# TOP.net
KiCad netlist of a schematic drawn in Altium Designer
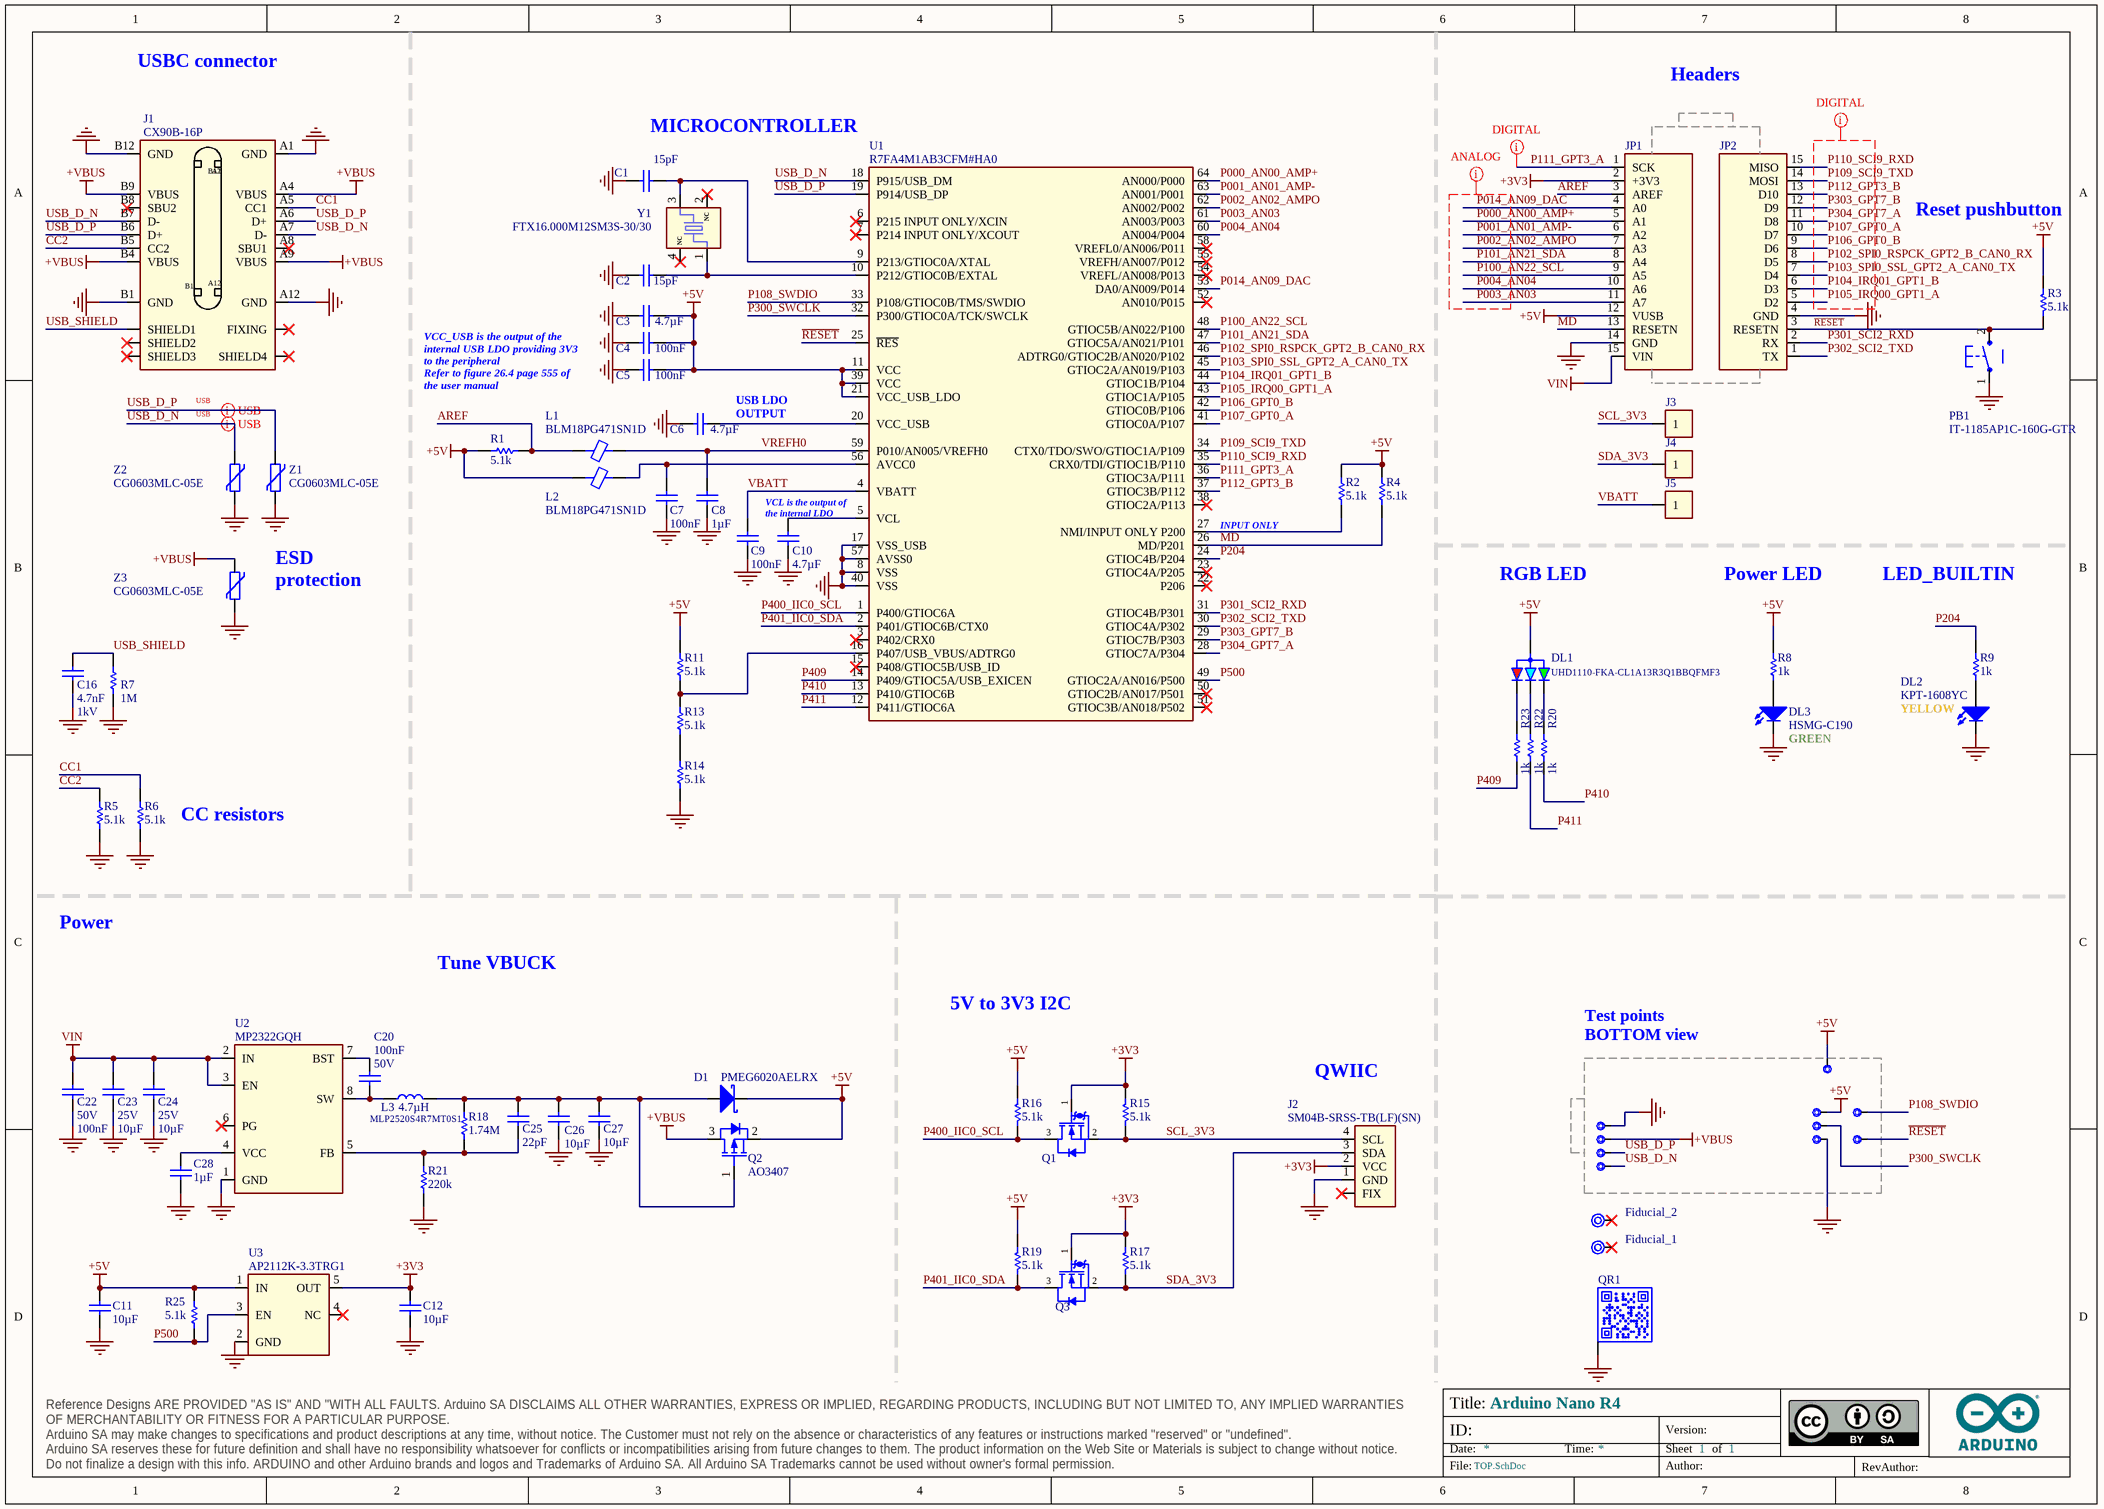
[diagram p0: TOP.SchDoc]

(export (version "E")
  (design (tool "Eeschema 10.0.6"))
  (components
    (comp (ref "3V3")
      (value "Test point 1.00mm")
      (footprint "TP-1.00MM")
      (fields (field (name "MANUFACTURER") "This is not a component"))
      (libsource (lib "Clean") (part "TESTPOINT"))
    )
    (comp (ref "C1")
      (value "15pF")
      (footprint "CAP-0402")
      (description "CAP CHIP 0402 15pF 5% 50V C0G")
      (fields (field (name "PART NUMBER") "C0402C150J5GACTU") (field (name "MANUFACTURER") "KEMET"))
      (libsource (lib "Clean") (part "CAP"))
    )
    (comp (ref "C2")
      (value "15pF")
      (footprint "CAP-0402")
      (description "CAP CHIP 0402 15pF 5% 50V C0G")
      (fields (field (name "PART NUMBER") "C0402C150J5GACTU") (field (name "MANUFACTURER") "KEMET"))
      (libsource (lib "Clean") (part "CAP"))
    )
    (comp (ref "C3")
      (value "4.7µF")
      (footprint "CAP-0402")
      (description "CAP CHIP 0402 4.7uF 20% 6V3 X5R")
      (fields (field (name "TOLERANCE") "20%") (field (name "MANUFACTURER") "Hottech"))
      (libsource (lib "Clean") (part "CAP"))
    )
    (comp (ref "C4")
      (value "100nF")
      (footprint "CAP-0402")
      (description "CAP CHIP 0402 100nF 10% 50V X5R")
      (fields (field (name "TOLERANCE") "10%") (field (name "MANUFACTURER") "Murata"))
      (libsource (lib "Clean") (part "CAP"))
    )
    (comp (ref "C5")
      (value "100nF")
      (footprint "CAP-0402")
      (description "CAP CHIP 0402 100nF 10% 50V X5R")
      (fields (field (name "TOLERANCE") "10%") (field (name "MANUFACTURER") "Murata"))
      (libsource (lib "Clean") (part "CAP"))
    )
    (comp (ref "C6")
      (value "4.7µF")
      (footprint "CAP-0402")
      (description "CAP CHIP 0402 4.7uF 20% 6V3 X5R")
      (fields (field (name "TOLERANCE") "20%") (field (name "MANUFACTURER") "Hottech"))
      (libsource (lib "Clean") (part "CAP"))
    )
    (comp (ref "C7")
      (value "100nF")
      (footprint "CAP-0402")
      (description "CAP CHIP 0402 100nF 10% 50V X5R")
      (fields (field (name "TOLERANCE") "10%") (field (name "MANUFACTURER") "Murata"))
      (libsource (lib "Clean") (part "CAP"))
    )
    (comp (ref "C8")
      (value "1µF")
      (footprint "CAP-0402")
      (description "CAP CHIP 0402 1uF 10% 10V X5R")
      (fields (field (name "TOLERANCE") "10%") (field (name "PART NUMBER") "CL05A105KP5NNNC"))
      (libsource (lib "Clean") (part "CAP"))
    )
    (comp (ref "C9")
      (value "100nF")
      (footprint "CAP-0402")
      (description "CAP CHIP 0402 100nF 10% 50V X5R")
      (fields (field (name "TOLERANCE") "10%") (field (name "MANUFACTURER") "Murata"))
      (libsource (lib "Clean") (part "CAP"))
    )
    (comp (ref "C10")
      (value "4.7µF")
      (footprint "CAP-0402")
      (description "CAP CHIP 0402 4.7uF 20% 6V3 X5R")
      (fields (field (name "TOLERANCE") "20%") (field (name "MANUFACTURER") "Hottech"))
      (libsource (lib "Clean") (part "CAP"))
    )
    (comp (ref "C11")
      (value "10µF")
      (footprint "CAP-0603")
      (description "CAP CHIP 0603 10uF 10% 10V X5R")
      (fields (field (name "MANUFACTURER") "Murata") (field (name "VOLTAGE") "10V"))
      (libsource (lib "Clean") (part "CAP"))
    )
    (comp (ref "C12")
      (value "10µF")
      (footprint "CAP-0603")
      (description "CAP CHIP 0603 10uF 10% 10V X5R")
      (fields (field (name "MANUFACTURER") "Murata") (field (name "VOLTAGE") "10V"))
      (libsource (lib "Clean") (part "CAP"))
    )
    (comp (ref "C16")
      (value "4.7nF")
      (footprint "CAP-0805")
      (description "CAP CHIP 0805 4.7nF 10% 1000V X7R")
      (fields
        (field (name "MANUFACTURER") "PSA Shenzen")
        (field (name "VOLTAGE") "1kV")
        (field (name "TOLERANCE") "10%")
      )
      (libsource (lib "Clean") (part "CAP"))
    )
    (comp (ref "C20")
      (value "100nF")
      (footprint "CAP-0402")
      (description "CAP CHIP 0402 100nF 10% 50V X5R")
      (fields
        (field (name "VOLTAGE") "50V")
        (field (name "PART NUMBER") "GRM155R61H104KE19D")
        (field (name "MANUFACTURER") "Murata")
      )
      (libsource (lib "Clean") (part "CAP"))
    )
    (comp (ref "C22")
      (value "100nF")
      (footprint "CAP-0402")
      (description "CAP CHIP 0402 100nF 10% 50V X5R")
      (fields
        (field (name "MANUFACTURER") "Murata")
        (field (name "PART NUMBER") "GRM155R61H104KE19D")
        (field (name "VOLTAGE") "50V")
      )
      (libsource (lib "Clean") (part "CAP"))
    )
    (comp (ref "C23")
      (value "10µF")
      (footprint "CAP-0603")
      (description "CAP CHIP 0603 10uF 20% 25V X5R")
      (fields
        (field (name "VOLTAGE") "25V")
        (field (name "PART NUMBER") "C1608A106M250NT")
        (field (name "TOLERANCE") "20%")
      )
      (libsource (lib "Clean") (part "CAP"))
    )
    (comp (ref "C24")
      (value "10µF")
      (footprint "CAP-0603")
      (description "CAP CHIP 0603 10uF 20% 25V X5R")
      (fields
        (field (name "VOLTAGE") "25V")
        (field (name "PART NUMBER") "C1608A106M250NT")
        (field (name "TOLERANCE") "20%")
      )
      (libsource (lib "Clean") (part "CAP"))
    )
    (comp (ref "C25")
      (value "22pF")
      (footprint "CAP-0402")
      (description "CAP CHIP 0402 22pF 5% 50V C0G")
      (fields (field (name "TOLERANCE") "5%") (field (name "PART NUMBER") "0402N220J500CT"))
      (libsource (lib "Clean") (part "CAP"))
    )
    (comp (ref "C26")
      (value "10µF")
      (footprint "CAP-0603")
      (description "CAP CHIP 0603 10uF 20% 25V X5R")
      (fields (field (name "VOLTAGE") "25V") (field (name "PART NUMBER") "C1608A106M250NT"))
      (libsource (lib "Clean") (part "CAP"))
    )
    (comp (ref "C27")
      (value "10µF")
      (footprint "CAP-0603")
      (description "CAP CHIP 0603 10uF 20% 25V X5R")
      (fields (field (name "VOLTAGE") "25V") (field (name "PART NUMBER") "C1608A106M250NT"))
      (libsource (lib "Clean") (part "CAP"))
    )
    (comp (ref "C28")
      (value "1µF")
      (footprint "CAP-0402")
      (description "CAP CHIP 0402 1uF 10% 50V X5R")
      (fields (field (name "TOLERANCE") "10%") (field (name "MANUFACTURER") "TDK"))
      (libsource (lib "Clean") (part "CAP"))
    )
    (comp (ref "D+1")
      (value "Test point 1.00mm")
      (footprint "TP-1.00MM")
      (fields (field (name "MANUFACTURER") "This is not a component"))
      (libsource (lib "Clean") (part "TESTPOINT"))
    )
    (comp (ref "D-1")
      (value "Test point 1.00mm")
      (footprint "TP-1.00MM")
      (fields (field (name "MANUFACTURER") "This is not a component"))
      (libsource (lib "Clean") (part "TESTPOINT"))
    )
    (comp (ref "D1")
      (value "PMEG6020AELRX")
      (footprint "SOD123-1")
      (description "DIODE SCHOTTKY SMD 2A 60V SOD123FL")
      (fields (field (name "MANUFACTURER") "Nexperia"))
      (libsource (lib "Clean") (part "PMEG6020AELRX"))
    )
    (comp (ref "DL1")
      (value "UHD1110-FKA-CL1A13R3Q1BBQFMF3")
      (footprint "UHD1110-FKA-CL1A13R3Q1BBQFMF3")
      (description "LED RGB BLACK BODY SMD")
      (fields (field (name "MANUFACTURER") "Cree LED"))
      (libsource (lib "Clean") (part "UHD1110-FKA-CL1A13R3Q1BBQFMF3"))
    )
    (comp (ref "DL2")
      (value "KPT-1608YC")
      (footprint "LEDC1608X80N-AK")
      (description "LED SMD 0603 GIA588   8mcd 120^")
      (fields (field (name "MANUFACTURER") "Kingbright"))
      (libsource (lib "Clean") (part "LED"))
    )
    (comp (ref "DL3")
      (value "HSMG-C190")
      (footprint "LEDC1608X80N-AK")
      (description "LED SMD 0603 GREEN/568 15mcd 120^")
      (fields (field (name "MANUFACTURER") "Broadcom"))
      (libsource (lib "Clean") (part "LED"))
    )
    (comp (ref "Fiducial_1")
      (value "Fiducial mark 1mm with 2mm solder")
      (footprint "Fiducial mark 1mm with circle-Footprint-1")
      (libsource (lib "Clean") (part "Fiducial mark 1mm with circle"))
    )
    (comp (ref "Fiducial_2")
      (value "Fiducial mark 1mm with 2mm solder")
      (footprint "Fiducial mark 1mm with circle-Footprint-1")
      (libsource (lib "Clean") (part "Fiducial mark 1mm with circle"))
    )
    (comp (ref "GND1")
      (value "Test point 1.00mm")
      (footprint "TP-1.00MM")
      (fields (field (name "MANUFACTURER") "This is not a component"))
      (libsource (lib "Clean") (part "TESTPOINT"))
    )
    (comp (ref "GND2")
      (value "Test point 1.00mm")
      (footprint "TP-1.00MM")
      (fields (field (name "MANUFACTURER") "This is not a component"))
      (libsource (lib "Clean") (part "TESTPOINT"))
    )
    (comp (ref "GPIO46")
      (value "Test point 1.00mm")
      (footprint "TP-1.00MM")
      (fields (field (name "MANUFACTURER") "This is not a component"))
      (libsource (lib "Clean") (part "TESTPOINT"))
    )
    (comp (ref "J1")
      (value "CX90B-16P")
      (footprint "CX90B-16P-Footprint-1")
      (description "CONN RCPT USB3.1 TYPEC 16POS SMD")
      (fields (field (name "MANUFACTURER") "Hirose"))
      (libsource (lib "Clean") (part "CX90B-16P-Symbol-1"))
    )
    (comp (ref "J2")
      (value "SM04B-SRSS-TB(LF)(SN)")
      (footprint "SM04B-SRSS-TB(LF)(SN)-Footprint-1")
      (description "CONN JST 4POS SIDE 1MM TIN QWIIC")
      (fields (field (name "MANUFACTURER") "JST"))
      (libsource (lib "Clean") (part "SM04B-SRSS-TB(LF)(SN)"))
    )
    (comp (ref "J3")
      (value "HEADER TH 2.54mm VERT. 1x001POS")
      (footprint "PIN HEADER 2.54mm VERT. 1x1POS")
      (libsource (lib "Clean") (part "PIN HEADER 2.54mm VERT. 1x1POS"))
    )
    (comp (ref "J4")
      (value "HEADER TH 2.54mm VERT. 1x001POS")
      (footprint "PIN HEADER 2.54mm VERT. 1x1POS")
      (libsource (lib "Clean") (part "PIN HEADER 2.54mm VERT. 1x1POS"))
    )
    (comp (ref "J5")
      (value "HEADER TH 2.54mm VERT. 1x001POS")
      (footprint "PIN HEADER 2.54mm VERT. 1x1POS")
      (libsource (lib "Clean") (part "PIN HEADER 2.54mm VERT. 1x1POS"))
    )
    (comp (ref "JP1")
      (value "PINHD-1X15-NANO-ANALOG-CASTELLATED")
      (footprint "PINHD-1X14_5VF")
      (description "CONN THD SOCKET F/1/D 15V JANALOG NANO-TYPE CASTELLATED")
      (libsource (lib "Clean") (part "PINHD-1X15-NANO-ANALOG-CASTELLATED"))
    )
    (comp (ref "JP2")
      (value "PINHD-1X15-NANO-DIGITAL-CASTELLATED")
      (footprint "PINHD-1X14_5VF")
      (description "CONN THD SOCKET F/1/D 15V JDIGITAL NANO-TYPE CASTELLATED")
      (libsource (lib "Clean") (part "PINHD-1X15-NANO-DIGITAL"))
    )
    (comp (ref "L1")
      (value "BLM18PG471SN1D")
      (footprint "L-0603")
      (description "FERRITE SMD 0603 470R 1A 0.2R")
      (fields (field (name "TOLERANCE") "25%") (field (name "MANUFACTURER") "Murata"))
      (libsource (lib "Clean") (part "Ferrite"))
    )
    (comp (ref "L2")
      (value "BLM18PG471SN1D")
      (footprint "L-0603")
      (description "FERRITE SMD 0603 470R 1A 0.2R")
      (fields (field (name "TOLERANCE") "25%") (field (name "MANUFACTURER") "Murata"))
      (libsource (lib "Clean") (part "Ferrite"))
    )
    (comp (ref "L3")
      (value "MLP2520S4R7MT0S1")
      (footprint "INDC2520X10L")
      (description "IND FIXED SMD 4.7UH 1A 130mOHM")
      (fields
        (field (name "TOLERANCE") "20%")
        (field (name "MANUFACTURER") "TDK")
        (field (name "ALTIUM_VALUE") "4.7µH")
      )
      (libsource (lib "Clean") (part "Inductor"))
    )
    (comp (ref "NC1")
      (value "Test point 1.00mm")
      (footprint "TP-1.00MM")
      (fields (field (name "MANUFACTURER") "This is not a component"))
      (libsource (lib "Clean") (part "TESTPOINT"))
    )
    (comp (ref "NC2")
      (value "Test point 1.00mm")
      (footprint "TP-1.00MM")
      (fields (field (name "MANUFACTURER") "This is not a component"))
      (libsource (lib "Clean") (part "TESTPOINT"))
    )
    (comp (ref "PB1")
      (value "IT-1185AP1C-160G-GTR")
      (footprint "C&K_PTS820_NO_HOLES-1")
      (description "PUSHBUTTON WHITE NO ANCHORS")
      (fields (field (name "MANUFACTURER") "Switronic"))
      (libsource (lib "Clean") (part "PTS820"))
    )
    (comp (ref "Q1")
      (value "2N7002KT1G")
      (footprint "SOT23")
      (description "MOSFET N-CH 60V 300mA ESD prot. SOT23")
      (fields (field (name "MANUFACTURER") "On Semiconductor"))
      (libsource (lib "Clean") (part "NMOS-2"))
    )
    (comp (ref "Q2")
      (value "AO3407")
      (footprint "SOT23-3")
      (description "MOSFET P-CH 30V 3.5A SOT23 VGSmin=1.4-2.4V RDSon max 87mOhm (-4.5V)")
      (fields (field (name "MANUFACTURER") "Hottech"))
      (libsource (lib "Clean") (part "AO3407"))
    )
    (comp (ref "Q3")
      (value "2N7002KT1G")
      (footprint "SOT23")
      (description "MOSFET N-CH 60V 300mA ESD prot. SOT23")
      (fields (field (name "MANUFACTURER") "On Semiconductor"))
      (libsource (lib "Clean") (part "NMOS-2"))
    )
    (comp (ref "QR1")
      (value "QR CODE 4x4mm")
      (footprint "QR CODE 4x4mm")
      (description "QR CODE 4x4mm on layer 34 (This is not a component)")
      (fields (field (name "PART NUMBER") "This is not a component"))
      (libsource (lib "Clean") (part "QR CODE 4x4mm"))
    )
    (comp (ref "R1")
      (value "5.1k")
      (footprint "RES-0402")
      (description "RES CHIP 0402 5k1 1% 1/16W")
      (fields (field (name "TOLERANCE") "1%") (field (name "POWER") "62.5mW"))
      (libsource (lib "Clean") (part "RES"))
    )
    (comp (ref "R2")
      (value "5.1k")
      (footprint "RES-0402")
      (description "RES CHIP 0402 5k1 1% 1/16W")
      (fields (field (name "TOLERANCE") "1%") (field (name "MANUFACTURER") "YAGEO"))
      (libsource (lib "Clean") (part "RES"))
    )
    (comp (ref "R3")
      (value "5.1k")
      (footprint "RES-0402")
      (description "RES CHIP 0402 5k1 1% 1/16W")
      (fields (field (name "PART NUMBER") "RC0402FR-075K1L") (field (name "MANUFACTURER") "YAGEO"))
      (libsource (lib "Clean") (part "RES"))
    )
    (comp (ref "R4")
      (value "5.1k")
      (footprint "RES-0402")
      (description "RES CHIP 0402 5k1 1% 1/16W")
      (fields (field (name "TOLERANCE") "1%") (field (name "MANUFACTURER") "YAGEO"))
      (libsource (lib "Clean") (part "RES"))
    )
    (comp (ref "R5")
      (value "5.1k")
      (footprint "RES-0402")
      (description "RES CHIP 0402 5k1 1% 1/16W")
      (fields (field (name "POWER") "62.5mW") (field (name "MANUFACTURER") "YAGEO"))
      (libsource (lib "Clean") (part "RES"))
    )
    (comp (ref "R6")
      (value "5.1k")
      (footprint "RES-0402")
      (description "RES CHIP 0402 5k1 1% 1/16W")
      (fields (field (name "POWER") "62.5mW") (field (name "MANUFACTURER") "YAGEO"))
      (libsource (lib "Clean") (part "RES"))
    )
    (comp (ref "R7")
      (value "1M")
      (footprint "RES-0402")
      (description "RES CHIP 0402 1M 1% 1/16W")
      (fields (field (name "MANUFACTURER") "Vishay") (field (name "POWER") "62.5mW"))
      (libsource (lib "Clean") (part "RES"))
    )
    (comp (ref "R8")
      (value "1k")
      (footprint "RES-0402")
      (description "RES CHIP 0402 1k 1% 1/16W")
      (fields (field (name "PART NUMBER") "CRCW04021K00FKEDC") (field (name "TOLERANCE") "1%"))
      (libsource (lib "Clean") (part "RES"))
    )
    (comp (ref "R9")
      (value "1k")
      (footprint "RES-0402")
      (description "RES CHIP 0402 1k 1% 1/16W")
      (fields (field (name "PART NUMBER") "CRCW04021K00FKEDC") (field (name "TOLERANCE") "1%"))
      (libsource (lib "Clean") (part "RES"))
    )
    (comp (ref "R11")
      (value "5.1k")
      (footprint "RES-0402")
      (description "RES CHIP 0402 5k1 1% 1/16W")
      (fields (field (name "PART NUMBER") "RC0402FR-075K1L") (field (name "MANUFACTURER") "YAGEO"))
      (libsource (lib "Clean") (part "RES"))
    )
    (comp (ref "R13")
      (value "5.1k")
      (footprint "RES-0402")
      (description "RES CHIP 0402 5k1 1% 1/16W")
      (fields (field (name "PART NUMBER") "RC0402FR-075K1L") (field (name "MANUFACTURER") "YAGEO"))
      (libsource (lib "Clean") (part "RES"))
    )
    (comp (ref "R14")
      (value "5.1k")
      (footprint "RES-0402")
      (description "RES CHIP 0402 5k1 1% 1/16W")
      (fields (field (name "PART NUMBER") "RC0402FR-075K1L") (field (name "MANUFACTURER") "YAGEO"))
      (libsource (lib "Clean") (part "RES"))
    )
    (comp (ref "R15")
      (value "5.1k")
      (footprint "RES-0402")
      (description "RES CHIP 0402 5k1 1% 1/16W")
      (fields (field (name "TOLERANCE") "1%") (field (name "MANUFACTURER") "YAGEO"))
      (libsource (lib "Clean") (part "RES"))
    )
    (comp (ref "R16")
      (value "5.1k")
      (footprint "RES-0402")
      (description "RES CHIP 0402 5k1 1% 1/16W")
      (fields (field (name "TOLERANCE") "1%") (field (name "MANUFACTURER") "YAGEO"))
      (libsource (lib "Clean") (part "RES"))
    )
    (comp (ref "R17")
      (value "5.1k")
      (footprint "RES-0402")
      (description "RES CHIP 0402 5k1 1% 1/16W")
      (fields (field (name "TOLERANCE") "1%") (field (name "MANUFACTURER") "YAGEO"))
      (libsource (lib "Clean") (part "RES"))
    )
    (comp (ref "R18")
      (value "1.74M")
      (footprint "RES-0402")
      (description "RES CHIP 0402 1.74M 1% 1/16W")
      (fields (field (name "MANUFACTURER") "YAGEO") (field (name "TOLERANCE") "1%"))
      (libsource (lib "Clean") (part "RES"))
    )
    (comp (ref "R19")
      (value "5.1k")
      (footprint "RES-0402")
      (description "RES CHIP 0402 5k1 1% 1/16W")
      (fields (field (name "TOLERANCE") "1%") (field (name "MANUFACTURER") "YAGEO"))
      (libsource (lib "Clean") (part "RES"))
    )
    (comp (ref "R20")
      (value "1k")
      (footprint "RES-0402")
      (description "RES CHIP 0402 1k 1% 1/16W")
      (fields (field (name "PART NUMBER") "CRCW04021K00FKEDC") (field (name "TOLERANCE") "1%"))
      (libsource (lib "Clean") (part "RES"))
    )
    (comp (ref "R21")
      (value "220k")
      (footprint "RES-0402")
      (description "RES CHIP 0402 220k 1% 1/16W")
      (fields (field (name "MANUFACTURER") "Vishay") (field (name "PART NUMBER") "CRCW0402220KFKED"))
      (libsource (lib "Clean") (part "RES"))
    )
    (comp (ref "R22")
      (value "1k")
      (footprint "RES-0402")
      (description "RES CHIP 0402 1k 1% 1/16W")
      (fields (field (name "PART NUMBER") "CRCW04021K00FKEDC") (field (name "TOLERANCE") "1%"))
      (libsource (lib "Clean") (part "RES"))
    )
    (comp (ref "R23")
      (value "1k")
      (footprint "RES-0402")
      (description "RES CHIP 0402 1k 1% 1/16W")
      (fields (field (name "PART NUMBER") "CRCW04021K00FKEDC") (field (name "TOLERANCE") "1%"))
      (libsource (lib "Clean") (part "RES"))
    )
    (comp (ref "R25")
      (value "5.1k")
      (footprint "RES-0402")
      (description "RES CHIP 0402 5k1 1% 1/16W")
      (fields (field (name "PART NUMBER") "RC0402FR-075K1L") (field (name "MANUFACTURER") "YAGEO"))
      (libsource (lib "Clean") (part "RES"))
    )
    (comp (ref "TP_VUSB")
      (value "Test point 1.00mm")
      (footprint "TP-1.00MM")
      (fields (field (name "MANUFACTURER") "This is not a component"))
      (libsource (lib "Clean") (part "TESTPOINT"))
    )
    (comp (ref "U1")
      (value "R7FA4M1AB3CFM#HA0")
      (footprint "CQFP50P1200X1200X170-64L")
      (description "IC uC RA4M1 32b M4 48MHz 254KB flash 32KB RAM 105°C LQFP64 10x10mm")
      (fields (field (name "MANUFACTURER") "Renesas"))
      (libsource (lib "Clean") (part "R7FA4M1AB3CFM#HA0"))
    )
    (comp (ref "U2")
      (value "MP2322GQH")
      (footprint "QFN50P150X200X90-8L")
      (description "IC STEP DOWN CONV 1A 22V QFN8")
      (fields (field (name "MANUFACTURER") "Monolithic Power Systems"))
      (libsource (lib "Clean") (part "MP2322GQH"))
    )
    (comp (ref "U3")
      (value "AP2112K-3.3TRG1")
      (footprint "SOT25")
      (description "IC LDO Vin max 6.5V Vout 3V3 Iout 600mA +EN  SOT25")
      (fields (field (name "MANUFACTURER") "Diodes Inc"))
      (libsource (lib "Clean") (part "AP2112K-3.3TRG1"))
    )
    (comp (ref "VUSB")
      (value "Test point 1.00mm")
      (footprint "TP-1.00MM")
      (fields (field (name "MANUFACTURER") "This is not a component"))
      (libsource (lib "Clean") (part "TESTPOINT"))
    )
    (comp (ref "Y1")
      (value "FTX16.000M12SM3S-30/30")
      (footprint "CRYSTAL_3.2x2.5mm_16MHz")
      (description "CRYSTAL 16.0000MHz 12pF SMD")
      (fields (field (name "MANUFACTURER") "Fronter Electronics"))
      (libsource (lib "Clean") (part "Crystal 4 pin 1-3"))
    )
    (comp (ref "Z1")
      (value "CG0603MLC-05E")
      (footprint "0603")
      (description "VARISTOR SMD 0603 VDC 5V ESD PROTECTION")
      (fields (field (name "MANUFACTURER") "Bourns") (field (name "VOLTAGE") "5V"))
      (libsource (lib "Clean") (part "Symbol"))
    )
    (comp (ref "Z2")
      (value "CG0603MLC-05E")
      (footprint "0603")
      (description "VARISTOR SMD 0603 VDC 5V ESD PROTECTION")
      (fields (field (name "MANUFACTURER") "Bourns") (field (name "VOLTAGE") "5V"))
      (libsource (lib "Clean") (part "Symbol"))
    )
    (comp (ref "Z3")
      (value "CG0603MLC-05E")
      (footprint "0603")
      (description "VARISTOR SMD 0603 VDC 5V ESD PROTECTION")
      (fields (field (name "MANUFACTURER") "Bourns") (field (name "VOLTAGE") "5V"))
      (libsource (lib "Clean") (part "Symbol"))
    )
  )
  (nets
    (net (code "1") (name "+3V3") (class "Default")
      (node (ref "C12") (pin "2") (pinfunction "2_2") (pintype "passive"))
      (node (ref "J2") (pin "2") (pinfunction "VCC_2") (pintype "passive"))
      (node (ref "JP1") (pin "2") (pinfunction "+3V3_2") (pintype "passive"))
      (node (ref "Q1") (pin "1") (pinfunction "G_1") (pintype "passive"))
      (node (ref "Q3") (pin "1") (pinfunction "G_1") (pintype "passive"))
      (node (ref "R15") (pin "1") (pinfunction "1_1") (pintype "passive"))
      (node (ref "R17") (pin "1") (pinfunction "1_1") (pintype "passive"))
      (node (ref "U3") (pin "5") (pinfunction "OUT_5") (pintype "power_in"))
    )
    (net (code "2") (name "+5V") (class "Default")
      (node (ref "3V3") (pin "X") (pinfunction "X_X") (pintype "passive"))
      (node (ref "C11") (pin "2") (pinfunction "2_2") (pintype "passive"))
      (node (ref "C3") (pin "2") (pinfunction "2_2") (pintype "passive"))
      (node (ref "C4") (pin "2") (pinfunction "2_2") (pintype "passive"))
      (node (ref "C5") (pin "2") (pinfunction "2_2") (pintype "passive"))
      (node (ref "D1") (pin "C") (pinfunction "C_C") (pintype "passive"))
      (node (ref "DL1") (pin "4") (pinfunction "ANODE_4") (pintype "passive"))
      (node (ref "JP1") (pin "12") (pinfunction "VUSB_12") (pintype "passive"))
      (node (ref "L2") (pin "1") (pinfunction "1_1") (pintype "passive"))
      (node (ref "Q2") (pin "2") (pinfunction "S_2") (pintype "passive"))
      (node (ref "R1") (pin "2") (pinfunction "2_2") (pintype "passive"))
      (node (ref "R11") (pin "2") (pinfunction "2_2") (pintype "passive"))
      (node (ref "R16") (pin "1") (pinfunction "1_1") (pintype "passive"))
      (node (ref "R19") (pin "1") (pinfunction "1_1") (pintype "passive"))
      (node (ref "R2") (pin "1") (pinfunction "1_1") (pintype "passive"))
      (node (ref "R25") (pin "2") (pinfunction "2_2") (pintype "passive"))
      (node (ref "R3") (pin "2") (pinfunction "2_2") (pintype "passive"))
      (node (ref "R4") (pin "1") (pinfunction "1_1") (pintype "passive"))
      (node (ref "R8") (pin "2") (pinfunction "2_2") (pintype "passive"))
      (node (ref "U1") (pin "11") (pinfunction "VCC_11") (pintype "passive"))
      (node (ref "U1") (pin "21") (pinfunction "VCC_USB_LDO_21") (pintype "passive"))
      (node (ref "U1") (pin "39") (pinfunction "VCC_39") (pintype "passive"))
      (node (ref "U3") (pin "1") (pinfunction "IN_1") (pintype "power_in"))
      (node (ref "VUSB") (pin "X") (pinfunction "X_X") (pintype "passive"))
    )
    (net (code "3") (name "+VBUS") (class "Default")
      (node (ref "J1") (pin "A4") (pinfunction "VBUS_A4") (pintype "passive"))
      (node (ref "J1") (pin "A9") (pinfunction "VBUS_A9") (pintype "passive"))
      (node (ref "J1") (pin "B4") (pinfunction "VBUS_B4") (pintype "passive"))
      (node (ref "J1") (pin "B9") (pinfunction "VBUS_B9") (pintype "passive"))
      (node (ref "Q2") (pin "3") (pinfunction "D_3") (pintype "passive"))
      (node (ref "TP_VUSB") (pin "X") (pinfunction "X_X") (pintype "passive"))
      (node (ref "Z3") (pin "1") (pinfunction "1_1") (pintype "passive"))
    )
    (net (code "4") (name "/AREF") (class "Default")
      (node (ref "JP1") (pin "3") (pinfunction "AREF_3") (pintype "passive"))
      (node (ref "L1") (pin "1") (pinfunction "1_1") (pintype "passive"))
      (node (ref "R1") (pin "1") (pinfunction "1_1") (pintype "passive"))
    )
    (net (code "5") (name "/CC1") (class "Default")
      (node (ref "J1") (pin "A5") (pinfunction "CC1_A5") (pintype "passive"))
      (node (ref "R6") (pin "2") (pinfunction "2_2") (pintype "passive"))
    )
    (net (code "6") (name "/CC2") (class "Default")
      (node (ref "J1") (pin "B5") (pinfunction "CC2_B5") (pintype "passive"))
      (node (ref "R5") (pin "2") (pinfunction "2_2") (pintype "passive"))
    )
    (net (code "7") (name "/MD") (class "Default")
      (node (ref "JP1") (pin "13") (pinfunction "RESETN_13") (pintype "passive"))
      (node (ref "R4") (pin "2") (pinfunction "2_2") (pintype "passive"))
      (node (ref "U1") (pin "26") (pinfunction "MD/P201_26") (pintype "passive"))
    )
    (net (code "8") (name "/P000_AN00_AMP+") (class "Default")
      (node (ref "JP1") (pin "5") (pinfunction "A1_5") (pintype "passive"))
      (node (ref "U1") (pin "64") (pinfunction "AN000/P000_64") (pintype "passive"))
    )
    (net (code "9") (name "/P001_AN01_AMP-") (class "Default")
      (node (ref "JP1") (pin "6") (pinfunction "A2_6") (pintype "passive"))
      (node (ref "U1") (pin "63") (pinfunction "AN001/P001_63") (pintype "passive"))
    )
    (net (code "10") (name "/P002_AN02_AMPO") (class "Default")
      (node (ref "JP1") (pin "7") (pinfunction "A3_7") (pintype "passive"))
      (node (ref "U1") (pin "62") (pinfunction "AN002/P002_62") (pintype "passive"))
    )
    (net (code "11") (name "/P003_AN03") (class "Default")
      (node (ref "JP1") (pin "11") (pinfunction "A7_11") (pintype "passive"))
      (node (ref "U1") (pin "61") (pinfunction "AN003/P003_61") (pintype "passive"))
    )
    (net (code "12") (name "/P004_AN04") (class "Default")
      (node (ref "JP1") (pin "10") (pinfunction "A6_10") (pintype "passive"))
      (node (ref "U1") (pin "60") (pinfunction "AN004/P004_60") (pintype "passive"))
    )
    (net (code "13") (name "/P014_AN09_DAC") (class "Default")
      (node (ref "JP1") (pin "4") (pinfunction "A0_4") (pintype "passive"))
      (node (ref "U1") (pin "53") (pinfunction "DA0/AN009/P014_53") (pintype "passive"))
    )
    (net (code "14") (name "/P100_AN22_SCL") (class "Default")
      (node (ref "JP1") (pin "9") (pinfunction "A5_9") (pintype "passive"))
      (node (ref "U1") (pin "48") (pinfunction "GTIOC5B/AN022/P100_48") (pintype "passive"))
    )
    (net (code "15") (name "/P101_AN21_SDA") (class "Default")
      (node (ref "JP1") (pin "8") (pinfunction "A4_8") (pintype "passive"))
      (node (ref "U1") (pin "47") (pinfunction "GTIOC5A/AN021/P101_47") (pintype "passive"))
    )
    (net (code "16") (name "/P102_SPI0_RSPCK_GPT2_B_CAN0_RX") (class "Default")
      (node (ref "JP2") (pin "8") (pinfunction "D5_8") (pintype "passive"))
      (node (ref "U1") (pin "46") (pinfunction "ADTRG0/GTIOC2B/AN020/P102_46") (pintype "passive"))
    )
    (net (code "17") (name "/P103_SPI0_SSL_GPT2_A_CAN0_TX") (class "Default")
      (node (ref "JP2") (pin "7") (pinfunction "D4_7") (pintype "passive"))
      (node (ref "U1") (pin "45") (pinfunction "GTIOC2A/AN019/P103_45") (pintype "passive"))
    )
    (net (code "18") (name "/P104_IRQ01_GPT1_B") (class "Default")
      (node (ref "JP2") (pin "6") (pinfunction "D3_6") (pintype "passive"))
      (node (ref "U1") (pin "44") (pinfunction "GTIOC1B/P104_44") (pintype "passive"))
    )
    (net (code "19") (name "/P105_IRQ00_GPT1_A") (class "Default")
      (node (ref "JP2") (pin "5") (pinfunction "D2_5") (pintype "passive"))
      (node (ref "U1") (pin "43") (pinfunction "GTIOC1A/P105_43") (pintype "passive"))
    )
    (net (code "20") (name "/P106_GPT0_B") (class "Default")
      (node (ref "JP2") (pin "9") (pinfunction "D6_9") (pintype "passive"))
      (node (ref "U1") (pin "42") (pinfunction "GTIOC0B/P106_42") (pintype "passive"))
    )
    (net (code "21") (name "/P107_GPT0_A") (class "Default")
      (node (ref "JP2") (pin "10") (pinfunction "D7_10") (pintype "passive"))
      (node (ref "U1") (pin "41") (pinfunction "GTIOC0A/P107_41") (pintype "passive"))
    )
    (net (code "22") (name "/P108_SWDIO") (class "Default")
      (node (ref "NC1") (pin "X") (pinfunction "X_X") (pintype "passive"))
      (node (ref "U1") (pin "33") (pinfunction "P108/GTIOC0B/TMS/SWDIO_33") (pintype "passive"))
    )
    (net (code "23") (name "/P109_SCI9_TXD") (class "Default")
      (node (ref "JP2") (pin "14") (pinfunction "MOSI_14") (pintype "passive"))
      (node (ref "U1") (pin "34") (pinfunction "CTX0/TDO/SWO/GTIOC1A/P109_34") (pintype "passive"))
    )
    (net (code "24") (name "/P110_SCI9_RXD") (class "Default")
      (node (ref "JP2") (pin "15") (pinfunction "MISO_15") (pintype "passive"))
      (node (ref "U1") (pin "35") (pinfunction "CRX0/TDI/GTIOC1B/P110_35") (pintype "passive"))
    )
    (net (code "25") (name "/P111_GPT3_A") (class "Default")
      (node (ref "JP1") (pin "1") (pinfunction "SCK_1") (pintype "passive"))
      (node (ref "U1") (pin "36") (pinfunction "GTIOC3A/P111_36") (pintype "passive"))
    )
    (net (code "26") (name "/P112_GPT3_B") (class "Default")
      (node (ref "JP2") (pin "13") (pinfunction "D10_13") (pintype "passive"))
      (node (ref "U1") (pin "37") (pinfunction "GTIOC3B/P112_37") (pintype "passive"))
    )
    (net (code "27") (name "/P204") (class "Default")
      (node (ref "R9") (pin "2") (pinfunction "2_2") (pintype "passive"))
      (node (ref "U1") (pin "24") (pinfunction "GTIOC4B/P204_24") (pintype "passive"))
    )
    (net (code "28") (name "/P300_SWCLK") (class "Default")
      (node (ref "GPIO46") (pin "X") (pinfunction "X_X") (pintype "passive"))
      (node (ref "U1") (pin "32") (pinfunction "P300/GTIOC0A/TCK/SWCLK_32") (pintype "passive"))
    )
    (net (code "29") (name "/P301_SCI2_RXD") (class "Default")
      (node (ref "JP2") (pin "2") (pinfunction "RX_2") (pintype "passive"))
      (node (ref "U1") (pin "31") (pinfunction "GTIOC4B/P301_31") (pintype "passive"))
    )
    (net (code "30") (name "/P302_SCI2_TXD") (class "Default")
      (node (ref "JP2") (pin "1") (pinfunction "TX_1") (pintype "passive"))
      (node (ref "U1") (pin "30") (pinfunction "GTIOC4A/P302_30") (pintype "passive"))
    )
    (net (code "31") (name "/P303_GPT7_B") (class "Default")
      (node (ref "JP2") (pin "12") (pinfunction "D9_12") (pintype "passive"))
      (node (ref "U1") (pin "29") (pinfunction "GTIOC7B/P303_29") (pintype "passive"))
    )
    (net (code "32") (name "/P304_GPT7_A") (class "Default")
      (node (ref "JP2") (pin "11") (pinfunction "D8_11") (pintype "passive"))
      (node (ref "U1") (pin "28") (pinfunction "GTIOC7A/P304_28") (pintype "passive"))
    )
    (net (code "33") (name "/P400_IIC0_SCL") (class "Default")
      (node (ref "Q1") (pin "3") (pinfunction "D_3") (pintype "passive"))
      (node (ref "R16") (pin "2") (pinfunction "2_2") (pintype "passive"))
      (node (ref "U1") (pin "1") (pinfunction "P400/GTIOC6A_1") (pintype "passive"))
    )
    (net (code "34") (name "/P401_IIC0_SDA") (class "Default")
      (node (ref "Q3") (pin "3") (pinfunction "D_3") (pintype "passive"))
      (node (ref "R19") (pin "2") (pinfunction "2_2") (pintype "passive"))
      (node (ref "U1") (pin "2") (pinfunction "P401/GTIOC6B/CTX0_2") (pintype "passive"))
    )
    (net (code "35") (name "/P409") (class "Default")
      (node (ref "R23") (pin "1") (pinfunction "1_1") (pintype "passive"))
      (node (ref "U1") (pin "14") (pinfunction "P409/GTIOC5A/USB_EXICEN_14") (pintype "passive"))
    )
    (net (code "36") (name "/P410") (class "Default")
      (node (ref "R20") (pin "1") (pinfunction "1_1") (pintype "passive"))
      (node (ref "U1") (pin "13") (pinfunction "P410/GTIOC6B_13") (pintype "passive"))
    )
    (net (code "37") (name "/P411") (class "Default")
      (node (ref "R22") (pin "1") (pinfunction "1_1") (pintype "passive"))
      (node (ref "U1") (pin "12") (pinfunction "P411/GTIOC6A_12") (pintype "passive"))
    )
    (net (code "38") (name "/P500") (class "Default")
      (node (ref "R25") (pin "1") (pinfunction "1_1") (pintype "passive"))
      (node (ref "U1") (pin "49") (pinfunction "GTIOC2A/AN016/P500_49") (pintype "passive"))
      (node (ref "U3") (pin "3") (pinfunction "EN_3") (pintype "passive"))
    )
    (net (code "39") (name "/SCL_3V3") (class "Default")
      (node (ref "J2") (pin "4") (pinfunction "SCL_4") (pintype "passive"))
      (node (ref "J3") (pin "1") (pinfunction "1_1") (pintype "passive"))
      (node (ref "Q1") (pin "2") (pinfunction "S_2") (pintype "passive"))
      (node (ref "R15") (pin "2") (pinfunction "2_2") (pintype "passive"))
    )
    (net (code "40") (name "/SDA_3V3") (class "Default")
      (node (ref "J2") (pin "3") (pinfunction "SDA_3") (pintype "passive"))
      (node (ref "J4") (pin "1") (pinfunction "1_1") (pintype "passive"))
      (node (ref "Q3") (pin "2") (pinfunction "S_2") (pintype "passive"))
      (node (ref "R17") (pin "2") (pinfunction "2_2") (pintype "passive"))
    )
    (net (code "41") (name "/USB_D_N") (class "Default")
      (node (ref "D-1") (pin "X") (pinfunction "X_X") (pintype "passive"))
      (node (ref "J1") (pin "A7") (pinfunction "D-_A7") (pintype "passive"))
      (node (ref "J1") (pin "B7") (pinfunction "D-_B7") (pintype "passive"))
      (node (ref "U1") (pin "18") (pinfunction "P915/USB_DM_18") (pintype "passive"))
      (node (ref "Z2") (pin "1") (pinfunction "1_1") (pintype "passive"))
    )
    (net (code "42") (name "/USB_D_P") (class "Default")
      (node (ref "D+1") (pin "X") (pinfunction "X_X") (pintype "passive"))
      (node (ref "J1") (pin "A6") (pinfunction "D+_A6") (pintype "passive"))
      (node (ref "J1") (pin "B6") (pinfunction "D+_B6") (pintype "passive"))
      (node (ref "U1") (pin "19") (pinfunction "P914/USB_DP_19") (pintype "passive"))
      (node (ref "Z1") (pin "1") (pinfunction "1_1") (pintype "passive"))
    )
    (net (code "43") (name "/USB_SHIELD") (class "Default")
      (node (ref "C16") (pin "2") (pinfunction "2_2") (pintype "passive"))
      (node (ref "J1") (pin "SHIELD1") (pinfunction "SHIELD1_SHIELD1") (pintype "passive"))
      (node (ref "R7") (pin "2") (pinfunction "2_2") (pintype "passive"))
    )
    (net (code "44") (name "/VBATT") (class "Default")
      (node (ref "C9") (pin "2") (pinfunction "2_2") (pintype "passive"))
      (node (ref "J5") (pin "1") (pinfunction "1_1") (pintype "passive"))
      (node (ref "U1") (pin "4") (pinfunction "VBATT_4") (pintype "passive"))
    )
    (net (code "45") (name "/VREFH0") (class "Default")
      (node (ref "C8") (pin "1") (pinfunction "1_1") (pintype "passive"))
      (node (ref "L1") (pin "2") (pinfunction "2_2") (pintype "passive"))
      (node (ref "U1") (pin "59") (pinfunction "P010/AN005/VREFH0_59") (pintype "passive"))
    )
    (net (code "46") (name "/~{RESET}") (class "Default")
      (node (ref "JP2") (pin "3") (pinfunction "RESETN_3") (pintype "passive"))
      (node (ref "NC2") (pin "X") (pinfunction "X_X") (pintype "passive"))
      (node (ref "PB1") (pin "2") (pinfunction "2_2") (pintype "passive"))
      (node (ref "R3") (pin "1") (pinfunction "1_1") (pintype "passive"))
      (node (ref "U1") (pin "25") (pinfunction "~{RES}_25") (pintype "passive"))
    )
    (net (code "47") (name "GND") (class "Default")
      (node (ref "C1") (pin "2") (pinfunction "2_2") (pintype "passive"))
      (node (ref "C10") (pin "1") (pinfunction "1_1") (pintype "passive"))
      (node (ref "C11") (pin "1") (pinfunction "1_1") (pintype "passive"))
      (node (ref "C12") (pin "1") (pinfunction "1_1") (pintype "passive"))
      (node (ref "C16") (pin "1") (pinfunction "1_1") (pintype "passive"))
      (node (ref "C2") (pin "2") (pinfunction "2_2") (pintype "passive"))
      (node (ref "C22") (pin "2") (pinfunction "2_2") (pintype "passive"))
      (node (ref "C23") (pin "1") (pinfunction "1_1") (pintype "passive"))
      (node (ref "C24") (pin "1") (pinfunction "1_1") (pintype "passive"))
      (node (ref "C26") (pin "1") (pinfunction "1_1") (pintype "passive"))
      (node (ref "C27") (pin "1") (pinfunction "1_1") (pintype "passive"))
      (node (ref "C28") (pin "1") (pinfunction "1_1") (pintype "passive"))
      (node (ref "C3") (pin "1") (pinfunction "1_1") (pintype "passive"))
      (node (ref "C4") (pin "1") (pinfunction "1_1") (pintype "passive"))
      (node (ref "C5") (pin "1") (pinfunction "1_1") (pintype "passive"))
      (node (ref "C6") (pin "1") (pinfunction "1_1") (pintype "passive"))
      (node (ref "C7") (pin "1") (pinfunction "1_1") (pintype "passive"))
      (node (ref "C8") (pin "2") (pinfunction "2_2") (pintype "passive"))
      (node (ref "C9") (pin "1") (pinfunction "1_1") (pintype "passive"))
      (node (ref "DL2") (pin "C") (pinfunction "C_C") (pintype "passive"))
      (node (ref "DL3") (pin "C") (pinfunction "C_C") (pintype "passive"))
      (node (ref "GND1") (pin "X") (pinfunction "X_X") (pintype "passive"))
      (node (ref "GND2") (pin "X") (pinfunction "X_X") (pintype "passive"))
      (node (ref "J1") (pin "A1") (pinfunction "GND_A1") (pintype "passive"))
      (node (ref "J1") (pin "A12") (pinfunction "GND_A12") (pintype "passive"))
      (node (ref "J1") (pin "B1") (pinfunction "GND_B1") (pintype "passive"))
      (node (ref "J1") (pin "B12") (pinfunction "GND_B12") (pintype "passive"))
      (node (ref "J2") (pin "1") (pinfunction "GND_1") (pintype "passive"))
      (node (ref "JP1") (pin "14") (pinfunction "GND_14") (pintype "passive"))
      (node (ref "JP2") (pin "4") (pinfunction "GND_4") (pintype "passive"))
      (node (ref "PB1") (pin "1") (pinfunction "1_1") (pintype "passive"))
      (node (ref "QR1") (pin "PAD") (pinfunction "PAD_PAD") (pintype "passive"))
      (node (ref "R14") (pin "1") (pinfunction "1_1") (pintype "passive"))
      (node (ref "R21") (pin "1") (pinfunction "1_1") (pintype "passive"))
      (node (ref "R5") (pin "1") (pinfunction "1_1") (pintype "passive"))
      (node (ref "R6") (pin "1") (pinfunction "1_1") (pintype "passive"))
      (node (ref "R7") (pin "1") (pinfunction "1_1") (pintype "passive"))
      (node (ref "U1") (pin "17") (pinfunction "VSS_USB_17") (pintype "passive"))
      (node (ref "U1") (pin "40") (pinfunction "VSS_40") (pintype "passive"))
      (node (ref "U1") (pin "57") (pinfunction "AVSS0_57") (pintype "passive"))
      (node (ref "U1") (pin "8") (pinfunction "VSS_8") (pintype "passive"))
      (node (ref "U2") (pin "1") (pinfunction "GND_1") (pintype "passive"))
      (node (ref "U3") (pin "2") (pinfunction "GND_2") (pintype "power_in"))
      (node (ref "Z1") (pin "2") (pinfunction "2_2") (pintype "passive"))
      (node (ref "Z2") (pin "2") (pinfunction "2_2") (pintype "passive"))
      (node (ref "Z3") (pin "2") (pinfunction "2_2") (pintype "passive"))
    )
    (net (code "48") (name "Net-(DL1-BLUE_C)") (class "Default")
      (node (ref "DL1") (pin "1") (pinfunction "BLUE_C_1") (pintype "passive"))
      (node (ref "R22") (pin "2") (pinfunction "2_2") (pintype "passive"))
    )
    (net (code "49") (name "Net-(DL1-GREEN_C)") (class "Default")
      (node (ref "DL1") (pin "2") (pinfunction "GREEN_C_2") (pintype "passive"))
      (node (ref "R20") (pin "2") (pinfunction "2_2") (pintype "passive"))
    )
    (net (code "50") (name "Net-(DL1-RED_C)") (class "Default")
      (node (ref "DL1") (pin "3") (pinfunction "RED_C_3") (pintype "passive"))
      (node (ref "R23") (pin "2") (pinfunction "2_2") (pintype "passive"))
    )
    (net (code "51") (name "Net-(DL2-PadA)") (class "Default")
      (node (ref "DL2") (pin "A") (pinfunction "A_A") (pintype "passive"))
      (node (ref "R9") (pin "1") (pinfunction "1_1") (pintype "passive"))
    )
    (net (code "52") (name "Net-(DL3-PadA)") (class "Default")
      (node (ref "DL3") (pin "A") (pinfunction "A_A") (pintype "passive"))
      (node (ref "R8") (pin "1") (pinfunction "1_1") (pintype "passive"))
    )
    (net (code "53") (name "Net-(Q2-G)") (class "Default")
      (node (ref "C25") (pin "2") (pinfunction "2_2") (pintype "passive"))
      (node (ref "C26") (pin "2") (pinfunction "2_2") (pintype "passive"))
      (node (ref "C27") (pin "2") (pinfunction "2_2") (pintype "passive"))
      (node (ref "D1") (pin "A") (pinfunction "A_A") (pintype "passive"))
      (node (ref "L3") (pin "2") (pinfunction "2_2") (pintype "passive"))
      (node (ref "Q2") (pin "1") (pinfunction "G_1") (pintype "passive"))
      (node (ref "R18") (pin "2") (pinfunction "2_2") (pintype "passive"))
    )
    (net (code "54") (name "Net-(R13-Pad1)") (class "Default")
      (node (ref "R13") (pin "1") (pinfunction "1_1") (pintype "passive"))
      (node (ref "R14") (pin "2") (pinfunction "2_2") (pintype "passive"))
    )
    (net (code "55") (name "Net-(U1-AVCC0)") (class "Default")
      (node (ref "C7") (pin "2") (pinfunction "2_2") (pintype "passive"))
      (node (ref "L2") (pin "2") (pinfunction "2_2") (pintype "passive"))
      (node (ref "U1") (pin "56") (pinfunction "AVCC0_56") (pintype "passive"))
    )
    (net (code "56") (name "Net-(U1-NMI{slash}INPUT_ONLY_P200)") (class "Default")
      (node (ref "R2") (pin "2") (pinfunction "2_2") (pintype "passive"))
      (node (ref "U1") (pin "27") (pinfunction "NMI/INPUT_ONLY_P200_27") (pintype "passive"))
    )
    (net (code "57") (name "Net-(U1-P212{slash}GTIOC0B{slash}EXTAL)") (class "Default")
      (node (ref "C2") (pin "1") (pinfunction "1_1") (pintype "passive"))
      (node (ref "U1") (pin "10") (pinfunction "P212/GTIOC0B/EXTAL_10") (pintype "passive"))
      (node (ref "Y1") (pin "1") (pinfunction "1_1") (pintype "passive"))
    )
    (net (code "58") (name "Net-(U1-P213{slash}GTIOC0A{slash}XTAL)") (class "Default")
      (node (ref "C1") (pin "1") (pinfunction "1_1") (pintype "passive"))
      (node (ref "U1") (pin "9") (pinfunction "P213/GTIOC0A/XTAL_9") (pintype "passive"))
      (node (ref "Y1") (pin "3") (pinfunction "3_3") (pintype "passive"))
    )
    (net (code "59") (name "Net-(U1-P407{slash}USB_VBUS{slash}ADTRG0)") (class "Default")
      (node (ref "R11") (pin "1") (pinfunction "1_1") (pintype "passive"))
      (node (ref "R13") (pin "2") (pinfunction "2_2") (pintype "passive"))
      (node (ref "U1") (pin "16") (pinfunction "P407/USB_VBUS/ADTRG0_16") (pintype "passive"))
    )
    (net (code "60") (name "Net-(U1-VCC_USB)") (class "Default")
      (node (ref "C6") (pin "2") (pinfunction "2_2") (pintype "passive"))
      (node (ref "U1") (pin "20") (pinfunction "VCC_USB_20") (pintype "passive"))
    )
    (net (code "61") (name "Net-(U1-VCL)") (class "Default")
      (node (ref "C10") (pin "2") (pinfunction "2_2") (pintype "passive"))
      (node (ref "U1") (pin "5") (pinfunction "VCL_5") (pintype "passive"))
    )
    (net (code "62") (name "Net-(U2-BST)") (class "Default")
      (node (ref "C20") (pin "2") (pinfunction "2_2") (pintype "passive"))
      (node (ref "U2") (pin "7") (pinfunction "BST_7") (pintype "passive"))
    )
    (net (code "63") (name "Net-(U2-FB)") (class "Default")
      (node (ref "C25") (pin "1") (pinfunction "1_1") (pintype "passive"))
      (node (ref "R18") (pin "1") (pinfunction "1_1") (pintype "passive"))
      (node (ref "R21") (pin "2") (pinfunction "2_2") (pintype "passive"))
      (node (ref "U2") (pin "5") (pinfunction "FB_5") (pintype "passive"))
    )
    (net (code "64") (name "Net-(U2-SW)") (class "Default")
      (node (ref "C20") (pin "1") (pinfunction "1_1") (pintype "passive"))
      (node (ref "L3") (pin "1") (pinfunction "1_1") (pintype "passive"))
      (node (ref "U2") (pin "8") (pinfunction "SW_8") (pintype "passive"))
    )
    (net (code "65") (name "Net-(U2-VCC)") (class "Default")
      (node (ref "C28") (pin "2") (pinfunction "2_2") (pintype "passive"))
      (node (ref "U2") (pin "4") (pinfunction "VCC_4") (pintype "passive"))
    )
    (net (code "66") (name "VIN") (class "Default")
      (node (ref "C22") (pin "1") (pinfunction "1_1") (pintype "passive"))
      (node (ref "C23") (pin "2") (pinfunction "2_2") (pintype "passive"))
      (node (ref "C24") (pin "2") (pinfunction "2_2") (pintype "passive"))
      (node (ref "JP1") (pin "15") (pinfunction "VIN_15") (pintype "passive"))
      (node (ref "U2") (pin "2") (pinfunction "IN_2") (pintype "passive"))
      (node (ref "U2") (pin "3") (pinfunction "EN_3") (pintype "passive"))
    )
    (net (code "67") (name "unconnected-(Fiducial_1-Pad1)") (class "Default")
      (node (ref "Fiducial_1") (pin "1") (pinfunction "1_1") (pintype "passive+no_connect"))
    )
    (net (code "68") (name "unconnected-(Fiducial_2-Pad1)") (class "Default")
      (node (ref "Fiducial_2") (pin "1") (pinfunction "1_1") (pintype "passive+no_connect"))
    )
    (net (code "69") (name "unconnected-(J1-PadFIXING)") (class "Default")
      (node (ref "J1") (pin "FIXING") (pinfunction "FIXING_FIXING") (pintype "passive+no_connect"))
    )
    (net (code "70") (name "unconnected-(J1-PadSHIELD2)") (class "Default")
      (node (ref "J1") (pin "SHIELD2") (pinfunction "SHIELD2_SHIELD2") (pintype "passive+no_connect"))
    )
    (net (code "71") (name "unconnected-(J1-PadSHIELD3)") (class "Default")
      (node (ref "J1") (pin "SHIELD3") (pinfunction "SHIELD3_SHIELD3") (pintype "passive+no_connect"))
    )
    (net (code "72") (name "unconnected-(J1-PadSHIELD4)") (class "Default")
      (node (ref "J1") (pin "SHIELD4") (pinfunction "SHIELD4_SHIELD4") (pintype "passive+no_connect"))
    )
    (net (code "73") (name "unconnected-(J1-SBU1-PadA8)") (class "Default")
      (node (ref "J1") (pin "A8") (pinfunction "SBU1_A8") (pintype "passive+no_connect"))
    )
    (net (code "74") (name "unconnected-(J1-SBU2-PadB8)") (class "Default")
      (node (ref "J1") (pin "B8") (pinfunction "SBU2_B8") (pintype "passive+no_connect"))
    )
    (net (code "75") (name "unconnected-(J2-PadFIX)") (class "Default")
      (node (ref "J2") (pin "FIX") (pinfunction "FIX_FIX") (pintype "passive+no_connect"))
    )
    (net (code "76") (name "unconnected-(U1-AN010{slash}P015-Pad52)") (class "Default")
      (node (ref "U1") (pin "52") (pinfunction "AN010/P015_52") (pintype "passive+no_connect"))
    )
    (net (code "77") (name "unconnected-(U1-GTIOC2A{slash}P113-Pad38)") (class "Default")
      (node (ref "U1") (pin "38") (pinfunction "GTIOC2A/P113_38") (pintype "passive+no_connect"))
    )
    (net (code "78") (name "unconnected-(U1-GTIOC2B{slash}AN017{slash}P501-Pad50)") (class "Default")
      (node (ref "U1") (pin "50") (pinfunction "GTIOC2B/AN017/P501_50") (pintype "passive+no_connect"))
    )
    (net (code "79") (name "unconnected-(U1-GTIOC3B{slash}AN018{slash}P502-Pad51)") (class "Default")
      (node (ref "U1") (pin "51") (pinfunction "GTIOC3B/AN018/P502_51") (pintype "passive+no_connect"))
    )
    (net (code "80") (name "unconnected-(U1-GTIOC4A{slash}P205-Pad23)") (class "Default")
      (node (ref "U1") (pin "23") (pinfunction "GTIOC4A/P205_23") (pintype "passive+no_connect"))
    )
    (net (code "81") (name "unconnected-(U1-P206-Pad22)") (class "Default")
      (node (ref "U1") (pin "22") (pinfunction "P206_22") (pintype "passive+no_connect"))
    )
    (net (code "82") (name "unconnected-(U1-P214_INPUT_ONLY{slash}XCOUT-Pad7)") (class "Default")
      (node (ref "U1") (pin "7") (pinfunction "P214_INPUT_ONLY/XCOUT_7") (pintype "passive+no_connect"))
    )
    (net (code "83") (name "unconnected-(U1-P215_INPUT_ONLY{slash}XCIN-Pad6)") (class "Default")
      (node (ref "U1") (pin "6") (pinfunction "P215_INPUT_ONLY/XCIN_6") (pintype "passive+no_connect"))
    )
    (net (code "84") (name "unconnected-(U1-P402{slash}CRX0-Pad3)") (class "Default")
      (node (ref "U1") (pin "3") (pinfunction "P402/CRX0_3") (pintype "passive+no_connect"))
    )
    (net (code "85") (name "unconnected-(U1-P408{slash}GTIOC5B{slash}USB_ID-Pad15)") (class "Default")
      (node (ref "U1") (pin "15") (pinfunction "P408/GTIOC5B/USB_ID_15") (pintype "passive+no_connect"))
    )
    (net (code "86") (name "unconnected-(U1-VREFH{slash}AN007{slash}P012-Pad55)") (class "Default")
      (node (ref "U1") (pin "55") (pinfunction "VREFH/AN007/P012_55") (pintype "passive+no_connect"))
    )
    (net (code "87") (name "unconnected-(U1-VREFL0{slash}AN006{slash}P011-Pad58)") (class "Default")
      (node (ref "U1") (pin "58") (pinfunction "VREFL0/AN006/P011_58") (pintype "passive+no_connect"))
    )
    (net (code "88") (name "unconnected-(U1-VREFL{slash}AN008{slash}P013-Pad54)") (class "Default")
      (node (ref "U1") (pin "54") (pinfunction "VREFL/AN008/P013_54") (pintype "passive+no_connect"))
    )
    (net (code "89") (name "unconnected-(U2-PG-Pad6)") (class "Default")
      (node (ref "U2") (pin "6") (pinfunction "PG_6") (pintype "passive+no_connect"))
    )
    (net (code "90") (name "unconnected-(U3-NC-Pad4)") (class "Default")
      (node (ref "U3") (pin "4") (pinfunction "NC_4") (pintype "power_in+no_connect"))
    )
    (net (code "91") (name "unconnected-(Y1-NC-Pad2)") (class "Default")
      (node (ref "Y1") (pin "2") (pinfunction "NC_2") (pintype "passive+no_connect"))
    )
    (net (code "92") (name "unconnected-(Y1-NC-Pad4)") (class "Default")
      (node (ref "Y1") (pin "4") (pinfunction "NC_4") (pintype "passive+no_connect"))
    )
  )
)
